# 3_-DCDC-4V2.net
KiCad netlist of a schematic drawn in Altium Designer
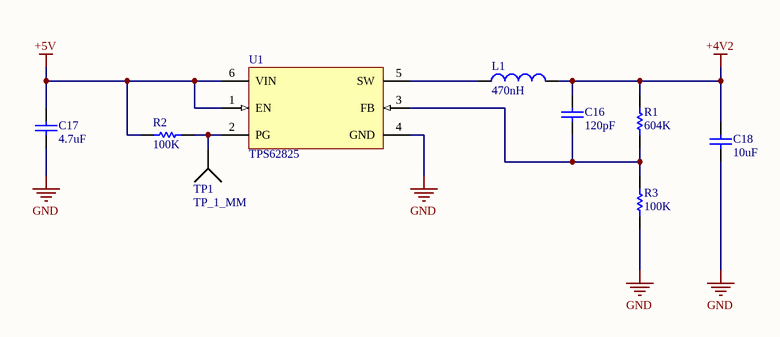
[diagram p0: [3]-DCDC-4V2.SchDoc]

(export (version "E")
  (design (tool "Eeschema 10.0.6"))
  (components
    (comp (ref "C16")
      (value "120pF")
      (footprint "CAPC1005N")
      (description "CAP CER 120PF 50V C0G/NP0 0402")
      (fields (field (name "TOLERANCE") "1 %") (field (name "VOLTAGE") "50V"))
      (libsource (lib "bitsnio") (part "GRM1555C1H121FA01D"))
    )
    (comp (ref "C17")
      (value "4.7uF")
      (footprint "CAPC2012N")
      (description "CAP CER 4.7UF 25V X5R 0805")
      (fields (field (name "TOLERANCE") "10%") (field (name "VOLTAGE") "25V"))
      (libsource (lib "bitsnio") (part "C2012X5R1E475K125AB"))
    )
    (comp (ref "C18")
      (value "10uF")
      (footprint "CAPC2012N")
      (description "CAP CER 10UF 10V X7R 0805")
      (fields (field (name "TOLERANCE") "10%") (field (name "VOLTAGE") "10V"))
      (libsource (lib "bitsnio") (part "C2012X7R1A106K125AC"))
    )
    (comp (ref "L1")
      (value "470nH")
      (footprint "IHLP-1212AE-11")
      (description "FIXED IND 470NH 6.7A 15 MOHM SMD")
      (fields (field (name "TOLERANCE") "20%"))
      (libsource (lib "bitsnio") (part "IHLP1212AEERR47M11"))
    )
    (comp (ref "R1")
      (value "604K")
      (footprint "RESC1005N")
      (description "RES SMD 604K OHM 1% 1/16W 0402")
      (fields (field (name "TOLERANCE") "1%"))
      (libsource (lib "bitsnio") (part "RC0402FR-07604KL"))
    )
    (comp (ref "R2")
      (value "100K")
      (footprint "RESC1005N")
      (description "RES SMD 100K OHM 1% 1/16W 0402")
      (fields (field (name "TOLERANCE") "1 %"))
      (libsource (lib "bitsnio") (part "RC0402FR-07100KL"))
    )
    (comp (ref "R3")
      (value "100K")
      (footprint "RESC1005N")
      (description "RES SMD 100K OHM 1% 1/16W 0402")
      (fields (field (name "TOLERANCE") "1 %"))
      (libsource (lib "bitsnio") (part "RC0402FR-07100KL"))
    )
    (comp (ref "TP1") (value "TP_1_MM") (footprint "TP_1_MM") (libsource (lib "bitsnio") (part "TP_1_MM")))
    (comp (ref "U1")
      (value "TPS62825")
      (footprint "DMQ0006A")
      (description "IC STEP DOWN CONV 1-5V 2A QFN")
      (libsource (lib "bitsnio") (part "IC_TPS62825DMQR"))
    )
  )
  (nets
    (net (code "1") (name "+4V2") (class "Default")
      (node (ref "C16") (pin "2") (pinfunction "2_2") (pintype "passive"))
      (node (ref "C18") (pin "2") (pinfunction "2_2") (pintype "passive"))
      (node (ref "L1") (pin "2") (pinfunction "2_2") (pintype "passive"))
      (node (ref "R1") (pin "2") (pinfunction "2_2") (pintype "passive"))
    )
    (net (code "2") (name "+5V") (class "Default")
      (node (ref "C17") (pin "2") (pinfunction "2_2") (pintype "passive"))
      (node (ref "R2") (pin "1") (pinfunction "1_1") (pintype "passive"))
      (node (ref "U1") (pin "1") (pinfunction "EN_1") (pintype "input"))
      (node (ref "U1") (pin "6") (pinfunction "VIN_6") (pintype "power_in"))
    )
    (net (code "3") (name "GND") (class "Default")
      (node (ref "C17") (pin "1") (pinfunction "1_1") (pintype "passive"))
      (node (ref "C18") (pin "1") (pinfunction "1_1") (pintype "passive"))
      (node (ref "R3") (pin "1") (pinfunction "1_1") (pintype "passive"))
      (node (ref "U1") (pin "4") (pinfunction "GND_4") (pintype "power_in"))
    )
    (net (code "4") (name "Net-(U1-FB)") (class "Default")
      (node (ref "C16") (pin "1") (pinfunction "1_1") (pintype "passive"))
      (node (ref "R1") (pin "1") (pinfunction "1_1") (pintype "passive"))
      (node (ref "R3") (pin "2") (pinfunction "2_2") (pintype "passive"))
      (node (ref "U1") (pin "3") (pinfunction "FB_3") (pintype "input"))
    )
    (net (code "5") (name "Net-(U1-PG)") (class "Default")
      (node (ref "R2") (pin "2") (pinfunction "2_2") (pintype "passive"))
      (node (ref "TP1") (pin "1") (pinfunction "1_1") (pintype "passive"))
      (node (ref "U1") (pin "2") (pinfunction "PG_2") (pintype "open_collector"))
    )
    (net (code "6") (name "Net-(U1-SW)") (class "Default")
      (node (ref "L1") (pin "1") (pinfunction "1_1") (pintype "passive"))
      (node (ref "U1") (pin "5") (pinfunction "SW_5") (pintype "power_in"))
    )
  )
)
